# MCU.net
KiCad netlist of a schematic drawn in Altium Designer
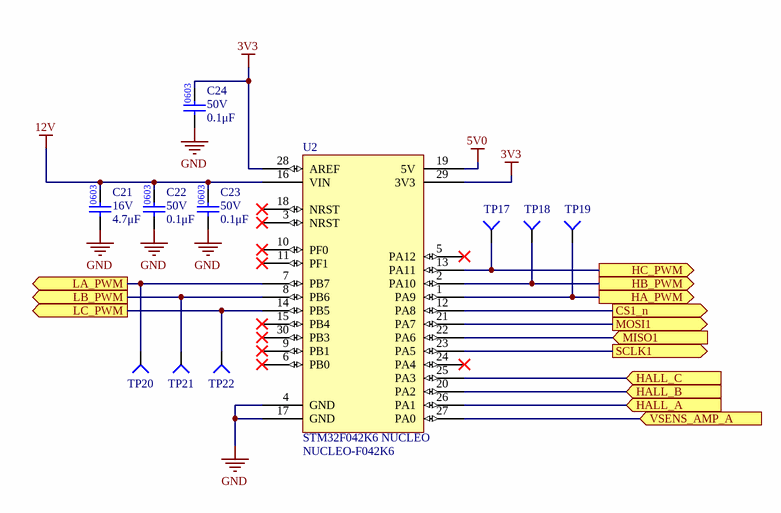
[diagram p0: MCU.SchDoc]

(export (version "E")
  (design (tool "Eeschema 10.0.6"))
  (components
    (comp (ref "C21")
      (value "4.7μF")
      (footprint "CAP0603")
      (description "CAP CER 4.7UF 16V X6S 0603")
      (fields (field (name "VOLTAGE RATING") "16V") (field (name "Comment") "CAP_4.7uF_16V_0603"))
      (libsource (lib "UWRT_Schematic_Library_2020") (part "CAP_4.7uF_16V_0603"))
    )
    (comp (ref "C22")
      (value "0.1μF")
      (footprint "CAP0603")
      (description "CAP CER 0.1UF 50V X7R 0603")
      (fields (field (name "VOLTAGE RATING") "50V") (field (name "Comment") "CAP_0.1uF_50V_0603"))
      (libsource (lib "UWRT_Schematic_Library_2020") (part "CAP_0.1uF_50V_0603"))
    )
    (comp (ref "C23")
      (value "0.1μF")
      (footprint "CAP0603")
      (description "CAP CER 0.1UF 50V X7R 0603")
      (fields (field (name "VOLTAGE RATING") "50V") (field (name "Comment") "CAP_0.1uF_50V_0603"))
      (libsource (lib "UWRT_Schematic_Library_2020") (part "CAP_0.1uF_50V_0603"))
    )
    (comp (ref "C24")
      (value "0.1μF")
      (footprint "CAP0603")
      (description "CAP CER 0.1UF 50V X7R 0603")
      (fields (field (name "VOLTAGE RATING") "50V") (field (name "Comment") "CAP_0.1uF_50V_0603"))
      (libsource (lib "UWRT_Schematic_Library_2020") (part "CAP_0.1uF_50V_0603"))
    )
    (comp (ref "TP17")
      (value "TESTPOINT_1MM_CIRCLE")
      (footprint "TESTPOINT_CIRCLE_1MM")
      (description "TESTPOINT 1MM CIRCLE")
      (libsource (lib "UWRT_Schematic_Library_2020") (part "TESTPOINT_1MM_CIRCLE"))
    )
    (comp (ref "TP18")
      (value "TESTPOINT_1MM_CIRCLE")
      (footprint "TESTPOINT_CIRCLE_1MM")
      (description "TESTPOINT 1MM CIRCLE")
      (libsource (lib "UWRT_Schematic_Library_2020") (part "TESTPOINT_1MM_CIRCLE"))
    )
    (comp (ref "TP19")
      (value "TESTPOINT_1MM_CIRCLE")
      (footprint "TESTPOINT_CIRCLE_1MM")
      (description "TESTPOINT 1MM CIRCLE")
      (libsource (lib "UWRT_Schematic_Library_2020") (part "TESTPOINT_1MM_CIRCLE"))
    )
    (comp (ref "TP20")
      (value "TESTPOINT_1MM_CIRCLE")
      (footprint "TESTPOINT_CIRCLE_1MM")
      (description "TESTPOINT 1MM CIRCLE")
      (libsource (lib "UWRT_Schematic_Library_2020") (part "TESTPOINT_1MM_CIRCLE"))
    )
    (comp (ref "TP21")
      (value "TESTPOINT_1MM_CIRCLE")
      (footprint "TESTPOINT_CIRCLE_1MM")
      (description "TESTPOINT 1MM CIRCLE")
      (libsource (lib "UWRT_Schematic_Library_2020") (part "TESTPOINT_1MM_CIRCLE"))
    )
    (comp (ref "TP22")
      (value "TESTPOINT_1MM_CIRCLE")
      (footprint "TESTPOINT_CIRCLE_1MM")
      (description "TESTPOINT 1MM CIRCLE")
      (libsource (lib "UWRT_Schematic_Library_2020") (part "TESTPOINT_1MM_CIRCLE"))
    )
    (comp (ref "U2")
      (value "STM32F042K6 NUCLEO")
      (footprint "NUCLEO-F042K6")
      (description "STM32 Nucleo-32 development board with STM32F042K6 MCU, supports Arduino connectivity")
      (fields
        (field (name "MANUFACTURER") "STMicroelectronics")
        (field (name "MANUFACTURER PART NUMBER") "NUCLEO-F042K6")
      )
      (libsource (lib "UWRT_Schematic_Library_2020") (part "STM32F042K6-NUCLEO"))
    )
  )
  (nets
    (net (code "1") (name "/CS1_n") (class "Default")
      (node (ref "U2") (pin "12") (pinfunction "PA8_12") (pintype "bidirectional"))
    )
    (net (code "2") (name "/HALL_A") (class "Default")
      (node (ref "U2") (pin "26") (pinfunction "PA1_26") (pintype "bidirectional"))
    )
    (net (code "3") (name "/HALL_B") (class "Default")
      (node (ref "U2") (pin "20") (pinfunction "PA2_20") (pintype "bidirectional"))
    )
    (net (code "4") (name "/HALL_C") (class "Default")
      (node (ref "U2") (pin "25") (pinfunction "PA3_25") (pintype "bidirectional"))
    )
    (net (code "5") (name "/HA_PWM") (class "Default")
      (node (ref "TP19") (pin "1") (pinfunction "=value_1") (pintype "passive"))
      (node (ref "U2") (pin "1") (pinfunction "PA9_1") (pintype "bidirectional"))
    )
    (net (code "6") (name "/HB_PWM") (class "Default")
      (node (ref "TP18") (pin "1") (pinfunction "=value_1") (pintype "passive"))
      (node (ref "U2") (pin "2") (pinfunction "PA10_2") (pintype "bidirectional"))
    )
    (net (code "7") (name "/HC_PWM") (class "Default")
      (node (ref "TP17") (pin "1") (pinfunction "=value_1") (pintype "passive"))
      (node (ref "U2") (pin "13") (pinfunction "PA11_13") (pintype "bidirectional"))
    )
    (net (code "8") (name "/LA_PWM") (class "Default")
      (node (ref "TP20") (pin "1") (pinfunction "=value_1") (pintype "passive"))
      (node (ref "U2") (pin "7") (pinfunction "PB7_7") (pintype "bidirectional"))
    )
    (net (code "9") (name "/LB_PWM") (class "Default")
      (node (ref "TP21") (pin "1") (pinfunction "=value_1") (pintype "passive"))
      (node (ref "U2") (pin "8") (pinfunction "PB6_8") (pintype "bidirectional"))
    )
    (net (code "10") (name "/LC_PWM") (class "Default")
      (node (ref "TP22") (pin "1") (pinfunction "=value_1") (pintype "passive"))
      (node (ref "U2") (pin "14") (pinfunction "PB5_14") (pintype "bidirectional"))
    )
    (net (code "11") (name "/MISO1") (class "Default")
      (node (ref "U2") (pin "22") (pinfunction "PA6_22") (pintype "bidirectional"))
    )
    (net (code "12") (name "/MOSI1") (class "Default")
      (node (ref "U2") (pin "21") (pinfunction "PA7_21") (pintype "bidirectional"))
    )
    (net (code "13") (name "/SCLK1") (class "Default")
      (node (ref "U2") (pin "23") (pinfunction "PA5_23") (pintype "bidirectional"))
    )
    (net (code "14") (name "/VSENS_AMP_A") (class "Default")
      (node (ref "U2") (pin "27") (pinfunction "PA0_27") (pintype "bidirectional"))
    )
    (net (code "15") (name "3V3") (class "Default")
      (node (ref "C24") (pin "2") (pinfunction "2_2") (pintype "passive"))
      (node (ref "U2") (pin "28") (pinfunction "AREF_28") (pintype "bidirectional"))
      (node (ref "U2") (pin "29") (pinfunction "3V3_29") (pintype "power_in"))
    )
    (net (code "16") (name "5V0") (class "Default")
      (node (ref "U2") (pin "19") (pinfunction "5V_19") (pintype "power_in"))
    )
    (net (code "17") (name "12V") (class "Default")
      (node (ref "C21") (pin "2") (pinfunction "2_2") (pintype "passive"))
      (node (ref "C22") (pin "2") (pinfunction "2_2") (pintype "passive"))
      (node (ref "C23") (pin "2") (pinfunction "2_2") (pintype "passive"))
      (node (ref "U2") (pin "16") (pinfunction "VIN_16") (pintype "power_in"))
    )
    (net (code "18") (name "GND") (class "Default")
      (node (ref "C21") (pin "1") (pinfunction "1_1") (pintype "passive"))
      (node (ref "C22") (pin "1") (pinfunction "1_1") (pintype "passive"))
      (node (ref "C23") (pin "1") (pinfunction "1_1") (pintype "passive"))
      (node (ref "C24") (pin "1") (pinfunction "1_1") (pintype "passive"))
      (node (ref "U2") (pin "17") (pinfunction "GND_17") (pintype "power_in"))
      (node (ref "U2") (pin "4") (pinfunction "GND_4") (pintype "power_in"))
    )
    (net (code "19") (name "unconnected-(U2-NRST-Pad3)") (class "Default")
      (node (ref "U2") (pin "3") (pinfunction "NRST_3") (pintype "bidirectional+no_connect"))
    )
    (net (code "20") (name "unconnected-(U2-NRST-Pad18)") (class "Default")
      (node (ref "U2") (pin "18") (pinfunction "NRST_18") (pintype "bidirectional+no_connect"))
    )
    (net (code "21") (name "unconnected-(U2-PA4-Pad24)") (class "Default")
      (node (ref "U2") (pin "24") (pinfunction "PA4_24") (pintype "bidirectional+no_connect"))
    )
    (net (code "22") (name "unconnected-(U2-PA12-Pad5)") (class "Default")
      (node (ref "U2") (pin "5") (pinfunction "PA12_5") (pintype "bidirectional+no_connect"))
    )
    (net (code "23") (name "unconnected-(U2-PB0-Pad6)") (class "Default")
      (node (ref "U2") (pin "6") (pinfunction "PB0_6") (pintype "bidirectional+no_connect"))
    )
    (net (code "24") (name "unconnected-(U2-PB1-Pad9)") (class "Default")
      (node (ref "U2") (pin "9") (pinfunction "PB1_9") (pintype "bidirectional+no_connect"))
    )
    (net (code "25") (name "unconnected-(U2-PB3-Pad30)") (class "Default")
      (node (ref "U2") (pin "30") (pinfunction "PB3_30") (pintype "bidirectional+no_connect"))
    )
    (net (code "26") (name "unconnected-(U2-PB4-Pad15)") (class "Default")
      (node (ref "U2") (pin "15") (pinfunction "PB4_15") (pintype "bidirectional+no_connect"))
    )
    (net (code "27") (name "unconnected-(U2-PF0-Pad10)") (class "Default")
      (node (ref "U2") (pin "10") (pinfunction "PF0_10") (pintype "bidirectional+no_connect"))
    )
    (net (code "28") (name "unconnected-(U2-PF1-Pad11)") (class "Default")
      (node (ref "U2") (pin "11") (pinfunction "PF1_11") (pintype "bidirectional+no_connect"))
    )
  )
)
